# etapa1_anger_X.net
KiCad netlist of a schematic drawn in Altium Designer
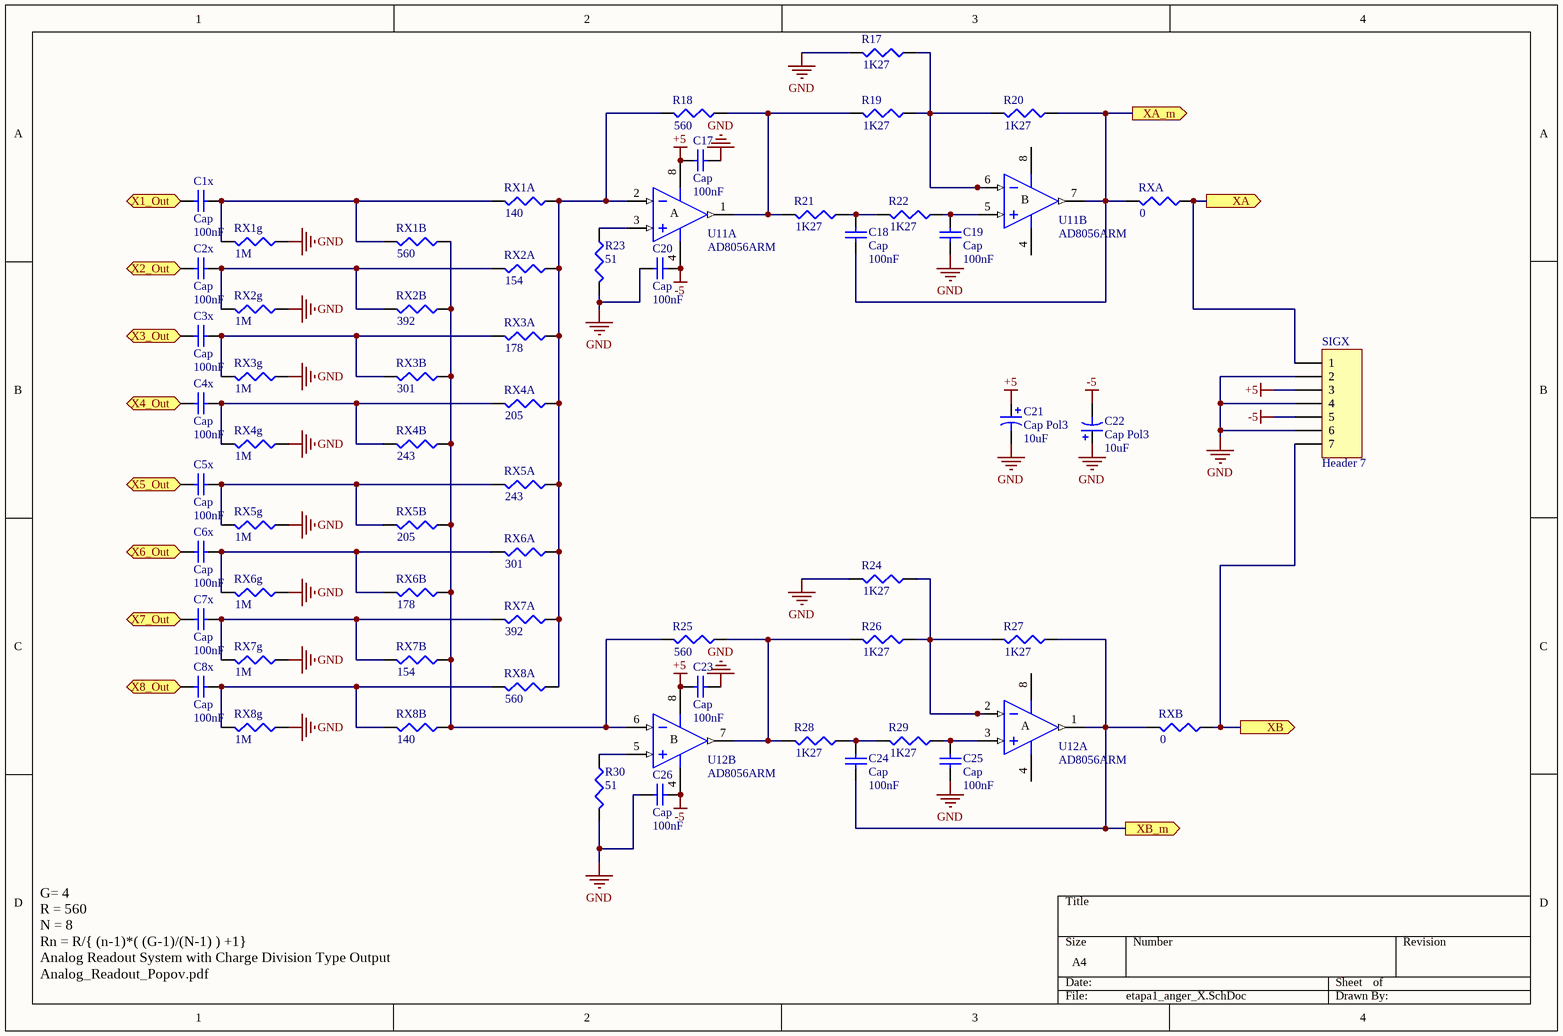
[diagram p0: etapa1_anger_X.SchDoc]

(export (version "E")
  (design (tool "Eeschema 10.0.6"))
  (components
    (comp (ref "C1x")
      (value "Cap")
      (footprint "1608[0603]")
      (description "Capacitor")
      (fields (field (name "ALTIUM_VALUE") "100nF") (field (name "PUBLISHER") "Altium Limited"))
      (libsource (lib "Miscellaneous Devices") (part "Cap"))
    )
    (comp (ref "C2x")
      (value "Cap")
      (footprint "1608[0603]")
      (description "Capacitor")
      (fields (field (name "ALTIUM_VALUE") "100nF") (field (name "PUBLISHER") "Altium Limited"))
      (libsource (lib "Miscellaneous Devices") (part "Cap"))
    )
    (comp (ref "C3x")
      (value "Cap")
      (footprint "1608[0603]")
      (description "Capacitor")
      (fields (field (name "ALTIUM_VALUE") "100nF") (field (name "PUBLISHER") "Altium Limited"))
      (libsource (lib "Miscellaneous Devices") (part "Cap"))
    )
    (comp (ref "C4x")
      (value "Cap")
      (footprint "1608[0603]")
      (description "Capacitor")
      (fields (field (name "ALTIUM_VALUE") "100nF") (field (name "PUBLISHER") "Altium Limited"))
      (libsource (lib "Miscellaneous Devices") (part "Cap"))
    )
    (comp (ref "C5x")
      (value "Cap")
      (footprint "1608[0603]")
      (description "Capacitor")
      (fields (field (name "ALTIUM_VALUE") "100nF") (field (name "PUBLISHER") "Altium Limited"))
      (libsource (lib "Miscellaneous Devices") (part "Cap"))
    )
    (comp (ref "C6x")
      (value "Cap")
      (footprint "1608[0603]")
      (description "Capacitor")
      (fields (field (name "ALTIUM_VALUE") "100nF") (field (name "PUBLISHER") "Altium Limited"))
      (libsource (lib "Miscellaneous Devices") (part "Cap"))
    )
    (comp (ref "C7x")
      (value "Cap")
      (footprint "1608[0603]")
      (description "Capacitor")
      (fields (field (name "ALTIUM_VALUE") "100nF") (field (name "PUBLISHER") "Altium Limited"))
      (libsource (lib "Miscellaneous Devices") (part "Cap"))
    )
    (comp (ref "C8x")
      (value "Cap")
      (footprint "1608[0603]")
      (description "Capacitor")
      (fields (field (name "ALTIUM_VALUE") "100nF") (field (name "PUBLISHER") "Altium Limited"))
      (libsource (lib "Miscellaneous Devices") (part "Cap"))
    )
    (comp (ref "C17")
      (value "Cap")
      (footprint "1608[0603]")
      (description "Capacitor")
      (fields (field (name "ALTIUM_VALUE") "100nF") (field (name "PUBLISHER") "Altium Limited"))
      (libsource (lib "Miscellaneous Devices") (part "Cap"))
    )
    (comp (ref "C18")
      (value "Cap")
      (footprint "1608[0603]")
      (description "Capacitor")
      (fields (field (name "ALTIUM_VALUE") "100nF") (field (name "PUBLISHER") "Altium Limited"))
      (libsource (lib "Miscellaneous Devices") (part "Cap"))
    )
    (comp (ref "C19")
      (value "Cap")
      (footprint "1608[0603]")
      (description "Capacitor")
      (fields (field (name "ALTIUM_VALUE") "100nF") (field (name "PUBLISHER") "Altium Limited"))
      (libsource (lib "Miscellaneous Devices") (part "Cap"))
    )
    (comp (ref "C20")
      (value "Cap")
      (footprint "1608[0603]")
      (description "Capacitor")
      (fields (field (name "ALTIUM_VALUE") "100nF") (field (name "PUBLISHER") "Altium Limited"))
      (libsource (lib "Miscellaneous Devices") (part "Cap"))
    )
    (comp (ref "C21")
      (value "Cap Pol3")
      (footprint "C0805")
      (description "Polarized Capacitor (Surface Mount)")
      (fields (field (name "ALTIUM_VALUE") "10uF") (field (name "PUBLISHER") "Altium Limited"))
      (libsource (lib "Miscellaneous Devices") (part "Cap Pol3"))
    )
    (comp (ref "C22")
      (value "Cap Pol3")
      (footprint "C0805")
      (description "Polarized Capacitor (Surface Mount)")
      (fields (field (name "ALTIUM_VALUE") "10uF") (field (name "PUBLISHER") "Altium Limited"))
      (libsource (lib "Miscellaneous Devices") (part "Cap Pol3"))
    )
    (comp (ref "C23")
      (value "Cap")
      (footprint "1608[0603]")
      (description "Capacitor")
      (fields (field (name "ALTIUM_VALUE") "100nF") (field (name "PUBLISHER") "Altium Limited"))
      (libsource (lib "Miscellaneous Devices") (part "Cap"))
    )
    (comp (ref "C24")
      (value "Cap")
      (footprint "1608[0603]")
      (description "Capacitor")
      (fields (field (name "ALTIUM_VALUE") "100nF") (field (name "PUBLISHER") "Altium Limited"))
      (libsource (lib "Miscellaneous Devices") (part "Cap"))
    )
    (comp (ref "C25")
      (value "Cap")
      (footprint "1608[0603]")
      (description "Capacitor")
      (fields (field (name "ALTIUM_VALUE") "100nF") (field (name "PUBLISHER") "Altium Limited"))
      (libsource (lib "Miscellaneous Devices") (part "Cap"))
    )
    (comp (ref "C26")
      (value "Cap")
      (footprint "1608[0603]")
      (description "Capacitor")
      (fields (field (name "ALTIUM_VALUE") "100nF") (field (name "PUBLISHER") "Altium Limited"))
      (libsource (lib "Miscellaneous Devices") (part "Cap"))
    )
    (comp (ref "R17")
      (value "1K27")
      (footprint "1608[0603]")
      (description "Resistor")
      (fields (field (name "Comment") "Res3") (field (name "PUBLISHER") "Altium Limited"))
      (libsource (lib "Miscellaneous Devices") (part "Res3"))
    )
    (comp (ref "R18")
      (value "560")
      (footprint "0402")
      (description "Resistor")
      (fields (field (name "Comment") "Res3") (field (name "PUBLISHER") "Altium Limited"))
      (libsource (lib "Miscellaneous Devices") (part "Res3"))
    )
    (comp (ref "R19")
      (value "1K27")
      (footprint "0402")
      (description "Resistor")
      (fields (field (name "Comment") "Res3") (field (name "PUBLISHER") "Altium Limited"))
      (libsource (lib "Miscellaneous Devices") (part "Res3"))
    )
    (comp (ref "R20")
      (value "1K27")
      (footprint "0402")
      (description "Resistor")
      (fields (field (name "Comment") "Res3") (field (name "PUBLISHER") "Altium Limited"))
      (libsource (lib "Miscellaneous Devices") (part "Res3"))
    )
    (comp (ref "R21")
      (value "1K27")
      (footprint "0402")
      (description "Resistor")
      (fields (field (name "Comment") "Res3") (field (name "PUBLISHER") "Altium Limited"))
      (libsource (lib "Miscellaneous Devices") (part "Res3"))
    )
    (comp (ref "R22")
      (value "1K27")
      (footprint "0402")
      (description "Resistor")
      (fields (field (name "Comment") "Res3") (field (name "PUBLISHER") "Altium Limited"))
      (libsource (lib "Miscellaneous Devices") (part "Res3"))
    )
    (comp (ref "R23")
      (value "51")
      (footprint "0402")
      (description "Resistor")
      (fields (field (name "Comment") "Res3") (field (name "PUBLISHER") "Altium Limited"))
      (libsource (lib "Miscellaneous Devices") (part "Res3"))
    )
    (comp (ref "R24")
      (value "1K27")
      (footprint "1608[0603]")
      (description "Resistor")
      (fields (field (name "Comment") "Res3") (field (name "PUBLISHER") "Altium Limited"))
      (libsource (lib "Miscellaneous Devices") (part "Res3"))
    )
    (comp (ref "R25")
      (value "560")
      (footprint "0402")
      (description "Resistor")
      (fields (field (name "Comment") "Res3") (field (name "PUBLISHER") "Altium Limited"))
      (libsource (lib "Miscellaneous Devices") (part "Res3"))
    )
    (comp (ref "R26")
      (value "1K27")
      (footprint "0402")
      (description "Resistor")
      (fields (field (name "Comment") "Res3") (field (name "PUBLISHER") "Altium Limited"))
      (libsource (lib "Miscellaneous Devices") (part "Res3"))
    )
    (comp (ref "R27")
      (value "1K27")
      (footprint "0402")
      (description "Resistor")
      (fields (field (name "Comment") "Res3") (field (name "PUBLISHER") "Altium Limited"))
      (libsource (lib "Miscellaneous Devices") (part "Res3"))
    )
    (comp (ref "R28")
      (value "1K27")
      (footprint "0402")
      (description "Resistor")
      (fields (field (name "Comment") "Res3") (field (name "PUBLISHER") "Altium Limited"))
      (libsource (lib "Miscellaneous Devices") (part "Res3"))
    )
    (comp (ref "R29")
      (value "1K27")
      (footprint "0402")
      (description "Resistor")
      (fields (field (name "Comment") "Res3") (field (name "PUBLISHER") "Altium Limited"))
      (libsource (lib "Miscellaneous Devices") (part "Res3"))
    )
    (comp (ref "R30")
      (value "51")
      (footprint "0402")
      (description "Resistor")
      (fields (field (name "Comment") "Res3") (field (name "PUBLISHER") "Altium Limited"))
      (libsource (lib "Miscellaneous Devices") (part "Res3"))
    )
    (comp (ref "RX1A")
      (value "140")
      (footprint "0402")
      (description "Resistor")
      (fields (field (name "Comment") "Res3") (field (name "PUBLISHER") "Altium Limited"))
      (libsource (lib "Miscellaneous Devices") (part "Res3"))
    )
    (comp (ref "RX1B")
      (value "560")
      (footprint "0402")
      (description "Resistor")
      (fields (field (name "Comment") "Res3") (field (name "PUBLISHER") "Altium Limited"))
      (libsource (lib "Miscellaneous Devices") (part "Res3"))
    )
    (comp (ref "RX1g")
      (value "1M")
      (footprint "J1-0603")
      (description "Resistor")
      (fields (field (name "Comment") "Res3") (field (name "PUBLISHER") "Altium Limited"))
      (libsource (lib "Miscellaneous Devices") (part "Res3"))
    )
    (comp (ref "RX2A")
      (value "154")
      (footprint "0402")
      (description "Resistor")
      (fields (field (name "Comment") "Res3") (field (name "PUBLISHER") "Altium Limited"))
      (libsource (lib "Miscellaneous Devices") (part "Res3"))
    )
    (comp (ref "RX2B")
      (value "392")
      (footprint "0402")
      (description "Resistor")
      (fields (field (name "Comment") "Res3") (field (name "PUBLISHER") "Altium Limited"))
      (libsource (lib "Miscellaneous Devices") (part "Res3"))
    )
    (comp (ref "RX2g")
      (value "1M")
      (footprint "J1-0603")
      (description "Resistor")
      (fields (field (name "Comment") "Res3") (field (name "PUBLISHER") "Altium Limited"))
      (libsource (lib "Miscellaneous Devices") (part "Res3"))
    )
    (comp (ref "RX3A")
      (value "178")
      (footprint "0402")
      (description "Resistor")
      (fields (field (name "Comment") "Res3") (field (name "PUBLISHER") "Altium Limited"))
      (libsource (lib "Miscellaneous Devices") (part "Res3"))
    )
    (comp (ref "RX3B")
      (value "301")
      (footprint "0402")
      (description "Resistor")
      (fields (field (name "Comment") "Res3") (field (name "PUBLISHER") "Altium Limited"))
      (libsource (lib "Miscellaneous Devices") (part "Res3"))
    )
    (comp (ref "RX3g")
      (value "1M")
      (footprint "J1-0603")
      (description "Resistor")
      (fields (field (name "Comment") "Res3") (field (name "PUBLISHER") "Altium Limited"))
      (libsource (lib "Miscellaneous Devices") (part "Res3"))
    )
    (comp (ref "RX4A")
      (value "205")
      (footprint "0402")
      (description "Resistor")
      (fields (field (name "Comment") "Res3") (field (name "PUBLISHER") "Altium Limited"))
      (libsource (lib "Miscellaneous Devices") (part "Res3"))
    )
    (comp (ref "RX4B")
      (value "243")
      (footprint "0402")
      (description "Resistor")
      (fields (field (name "Comment") "Res3") (field (name "PUBLISHER") "Altium Limited"))
      (libsource (lib "Miscellaneous Devices") (part "Res3"))
    )
    (comp (ref "RX4g")
      (value "1M")
      (footprint "J1-0603")
      (description "Resistor")
      (fields (field (name "Comment") "Res3") (field (name "PUBLISHER") "Altium Limited"))
      (libsource (lib "Miscellaneous Devices") (part "Res3"))
    )
    (comp (ref "RX5A")
      (value "243")
      (footprint "0402")
      (description "Resistor")
      (fields (field (name "Comment") "Res3") (field (name "PUBLISHER") "Altium Limited"))
      (libsource (lib "Miscellaneous Devices") (part "Res3"))
    )
    (comp (ref "RX5B")
      (value "205")
      (footprint "0402")
      (description "Resistor")
      (fields (field (name "Comment") "Res3") (field (name "PUBLISHER") "Altium Limited"))
      (libsource (lib "Miscellaneous Devices") (part "Res3"))
    )
    (comp (ref "RX5g")
      (value "1M")
      (footprint "J1-0603")
      (description "Resistor")
      (fields (field (name "Comment") "Res3") (field (name "PUBLISHER") "Altium Limited"))
      (libsource (lib "Miscellaneous Devices") (part "Res3"))
    )
    (comp (ref "RX6A")
      (value "301")
      (footprint "0402")
      (description "Resistor")
      (fields (field (name "Comment") "Res3") (field (name "PUBLISHER") "Altium Limited"))
      (libsource (lib "Miscellaneous Devices") (part "Res3"))
    )
    (comp (ref "RX6B")
      (value "178")
      (footprint "0402")
      (description "Resistor")
      (fields (field (name "Comment") "Res3") (field (name "PUBLISHER") "Altium Limited"))
      (libsource (lib "Miscellaneous Devices") (part "Res3"))
    )
    (comp (ref "RX6g")
      (value "1M")
      (footprint "J1-0603")
      (description "Resistor")
      (fields (field (name "Comment") "Res3") (field (name "PUBLISHER") "Altium Limited"))
      (libsource (lib "Miscellaneous Devices") (part "Res3"))
    )
    (comp (ref "RX7A")
      (value "392")
      (footprint "0402")
      (description "Resistor")
      (fields (field (name "Comment") "Res3") (field (name "PUBLISHER") "Altium Limited"))
      (libsource (lib "Miscellaneous Devices") (part "Res3"))
    )
    (comp (ref "RX7B")
      (value "154")
      (footprint "0402")
      (description "Resistor")
      (fields (field (name "Comment") "Res3") (field (name "PUBLISHER") "Altium Limited"))
      (libsource (lib "Miscellaneous Devices") (part "Res3"))
    )
    (comp (ref "RX7g")
      (value "1M")
      (footprint "J1-0603")
      (description "Resistor")
      (fields (field (name "Comment") "Res3") (field (name "PUBLISHER") "Altium Limited"))
      (libsource (lib "Miscellaneous Devices") (part "Res3"))
    )
    (comp (ref "RX8A")
      (value "560")
      (footprint "0402")
      (description "Resistor")
      (fields (field (name "Comment") "Res3") (field (name "PUBLISHER") "Altium Limited"))
      (libsource (lib "Miscellaneous Devices") (part "Res3"))
    )
    (comp (ref "RX8B")
      (value "140")
      (footprint "0402")
      (description "Resistor")
      (fields (field (name "Comment") "Res3") (field (name "PUBLISHER") "Altium Limited"))
      (libsource (lib "Miscellaneous Devices") (part "Res3"))
    )
    (comp (ref "RX8g")
      (value "1M")
      (footprint "J1-0603")
      (description "Resistor")
      (fields (field (name "Comment") "Res3") (field (name "PUBLISHER") "Altium Limited"))
      (libsource (lib "Miscellaneous Devices") (part "Res3"))
    )
    (comp (ref "RXA")
      (value "0")
      (footprint "0402")
      (description "Resistor")
      (fields (field (name "Comment") "Res3") (field (name "PUBLISHER") "Altium Limited"))
      (libsource (lib "Miscellaneous Devices") (part "Res3"))
    )
    (comp (ref "RXB")
      (value "0")
      (footprint "0402")
      (description "Resistor")
      (fields (field (name "Comment") "Res3") (field (name "PUBLISHER") "Altium Limited"))
      (libsource (lib "Miscellaneous Devices") (part "Res3"))
    )
    (comp (ref "SIGX")
      (value "Header 7")
      (footprint "HDR1X7")
      (description "Header, 7-Pin")
      (fields (field (name "PUBLISHER") "Altium Limited"))
      (libsource (lib "Miscellaneous Connectors") (part "Header 7"))
    )
    (comp (ref "U11")
      (value "AD8056ARM")
      (footprint "RM-8")
      (description "Low Cost, 300MHz Voltage Feedback Amplifier")
      (fields (field (name "PUBLISHER") "Altium Limited"))
      (libsource (lib "AD Operational Amplifier") (part "AD8056ARM"))
    )
    (comp (ref "U12")
      (value "AD8056ARM")
      (footprint "RM-8")
      (description "Low Cost, 300MHz Voltage Feedback Amplifier")
      (fields (field (name "PUBLISHER") "Altium Limited"))
      (libsource (lib "AD Operational Amplifier") (part "AD8056ARM"))
    )
  )
  (nets
    (net (code "1") (name "+5") (class "Default")
      (node (ref "C17") (pin "1") (pinfunction "1_1") (pintype "passive"))
      (node (ref "C21") (pin "1") (pinfunction "1_1") (pintype "passive"))
      (node (ref "C23") (pin "1") (pinfunction "1_1") (pintype "passive"))
      (node (ref "SIGX") (pin "3") (pinfunction "3_3") (pintype "passive"))
      (node (ref "U11") (pin "8") (pinfunction "V+_8") (pintype "power_in"))
      (node (ref "U12") (pin "8") (pinfunction "V+_8") (pintype "power_in"))
    )
    (net (code "2") (name "-5") (class "Default")
      (node (ref "C20") (pin "2") (pinfunction "2_2") (pintype "passive"))
      (node (ref "C22") (pin "2") (pinfunction "2_2") (pintype "passive"))
      (node (ref "C26") (pin "2") (pinfunction "2_2") (pintype "passive"))
      (node (ref "SIGX") (pin "5") (pinfunction "5_5") (pintype "passive"))
      (node (ref "U11") (pin "4") (pinfunction "V-_4") (pintype "power_in"))
      (node (ref "U12") (pin "4") (pinfunction "V-_4") (pintype "power_in"))
    )
    (net (code "3") (name "/X1_Out") (class "Default")
      (node (ref "C1x") (pin "1") (pinfunction "1_1") (pintype "passive"))
    )
    (net (code "4") (name "/X2_Out") (class "Default")
      (node (ref "C2x") (pin "1") (pinfunction "1_1") (pintype "passive"))
    )
    (net (code "5") (name "/X3_Out") (class "Default")
      (node (ref "C3x") (pin "1") (pinfunction "1_1") (pintype "passive"))
    )
    (net (code "6") (name "/X4_Out") (class "Default")
      (node (ref "C4x") (pin "1") (pinfunction "1_1") (pintype "passive"))
    )
    (net (code "7") (name "/X5_Out") (class "Default")
      (node (ref "C5x") (pin "1") (pinfunction "1_1") (pintype "passive"))
    )
    (net (code "8") (name "/X6_Out") (class "Default")
      (node (ref "C6x") (pin "1") (pinfunction "1_1") (pintype "passive"))
    )
    (net (code "9") (name "/X7_Out") (class "Default")
      (node (ref "C7x") (pin "1") (pinfunction "1_1") (pintype "passive"))
    )
    (net (code "10") (name "/X8_Out") (class "Default")
      (node (ref "C8x") (pin "1") (pinfunction "1_1") (pintype "passive"))
    )
    (net (code "11") (name "/XA") (class "Default")
      (node (ref "RXA") (pin "1") (pinfunction "1_1") (pintype "passive"))
      (node (ref "SIGX") (pin "1") (pinfunction "1_1") (pintype "passive"))
    )
    (net (code "12") (name "/XA_m") (class "Default")
      (node (ref "C18") (pin "2") (pinfunction "2_2") (pintype "passive"))
      (node (ref "R20") (pin "1") (pinfunction "1_1") (pintype "passive"))
      (node (ref "RXA") (pin "2") (pinfunction "2_2") (pintype "passive"))
      (node (ref "U11") (pin "7") (pinfunction "OUT_7") (pintype "output"))
    )
    (net (code "13") (name "/XB") (class "Default")
      (node (ref "RXB") (pin "1") (pinfunction "1_1") (pintype "passive"))
      (node (ref "SIGX") (pin "7") (pinfunction "7_7") (pintype "passive"))
    )
    (net (code "14") (name "/XB_m") (class "Default")
      (node (ref "C24") (pin "2") (pinfunction "2_2") (pintype "passive"))
      (node (ref "R27") (pin "1") (pinfunction "1_1") (pintype "passive"))
      (node (ref "RXB") (pin "2") (pinfunction "2_2") (pintype "passive"))
      (node (ref "U12") (pin "1") (pinfunction "OUT_1") (pintype "output"))
    )
    (net (code "15") (name "GND") (class "Default")
      (node (ref "C17") (pin "2") (pinfunction "2_2") (pintype "passive"))
      (node (ref "C19") (pin "2") (pinfunction "2_2") (pintype "passive"))
      (node (ref "C20") (pin "1") (pinfunction "1_1") (pintype "passive"))
      (node (ref "C21") (pin "2") (pinfunction "2_2") (pintype "passive"))
      (node (ref "C22") (pin "1") (pinfunction "1_1") (pintype "passive"))
      (node (ref "C23") (pin "2") (pinfunction "2_2") (pintype "passive"))
      (node (ref "C25") (pin "2") (pinfunction "2_2") (pintype "passive"))
      (node (ref "C26") (pin "1") (pinfunction "1_1") (pintype "passive"))
      (node (ref "R17") (pin "2") (pinfunction "2_2") (pintype "passive"))
      (node (ref "R23") (pin "2") (pinfunction "2_2") (pintype "passive"))
      (node (ref "R24") (pin "2") (pinfunction "2_2") (pintype "passive"))
      (node (ref "R30") (pin "2") (pinfunction "2_2") (pintype "passive"))
      (node (ref "RX1g") (pin "1") (pinfunction "1_1") (pintype "passive"))
      (node (ref "RX2g") (pin "1") (pinfunction "1_1") (pintype "passive"))
      (node (ref "RX3g") (pin "1") (pinfunction "1_1") (pintype "passive"))
      (node (ref "RX4g") (pin "1") (pinfunction "1_1") (pintype "passive"))
      (node (ref "RX5g") (pin "1") (pinfunction "1_1") (pintype "passive"))
      (node (ref "RX6g") (pin "1") (pinfunction "1_1") (pintype "passive"))
      (node (ref "RX7g") (pin "1") (pinfunction "1_1") (pintype "passive"))
      (node (ref "RX8g") (pin "1") (pinfunction "1_1") (pintype "passive"))
      (node (ref "SIGX") (pin "2") (pinfunction "2_2") (pintype "passive"))
      (node (ref "SIGX") (pin "4") (pinfunction "4_4") (pintype "passive"))
      (node (ref "SIGX") (pin "6") (pinfunction "6_6") (pintype "passive"))
    )
    (net (code "16") (name "Net-(C1x-Pad2)") (class "Default")
      (node (ref "C1x") (pin "2") (pinfunction "2_2") (pintype "passive"))
      (node (ref "RX1A") (pin "2") (pinfunction "2_2") (pintype "passive"))
      (node (ref "RX1B") (pin "2") (pinfunction "2_2") (pintype "passive"))
      (node (ref "RX1g") (pin "2") (pinfunction "2_2") (pintype "passive"))
    )
    (net (code "17") (name "Net-(C2x-Pad2)") (class "Default")
      (node (ref "C2x") (pin "2") (pinfunction "2_2") (pintype "passive"))
      (node (ref "RX2A") (pin "2") (pinfunction "2_2") (pintype "passive"))
      (node (ref "RX2B") (pin "2") (pinfunction "2_2") (pintype "passive"))
      (node (ref "RX2g") (pin "2") (pinfunction "2_2") (pintype "passive"))
    )
    (net (code "18") (name "Net-(C3x-Pad2)") (class "Default")
      (node (ref "C3x") (pin "2") (pinfunction "2_2") (pintype "passive"))
      (node (ref "RX3A") (pin "2") (pinfunction "2_2") (pintype "passive"))
      (node (ref "RX3B") (pin "2") (pinfunction "2_2") (pintype "passive"))
      (node (ref "RX3g") (pin "2") (pinfunction "2_2") (pintype "passive"))
    )
    (net (code "19") (name "Net-(C4x-Pad2)") (class "Default")
      (node (ref "C4x") (pin "2") (pinfunction "2_2") (pintype "passive"))
      (node (ref "RX4A") (pin "2") (pinfunction "2_2") (pintype "passive"))
      (node (ref "RX4B") (pin "2") (pinfunction "2_2") (pintype "passive"))
      (node (ref "RX4g") (pin "2") (pinfunction "2_2") (pintype "passive"))
    )
    (net (code "20") (name "Net-(C5x-Pad2)") (class "Default")
      (node (ref "C5x") (pin "2") (pinfunction "2_2") (pintype "passive"))
      (node (ref "RX5A") (pin "2") (pinfunction "2_2") (pintype "passive"))
      (node (ref "RX5B") (pin "2") (pinfunction "2_2") (pintype "passive"))
      (node (ref "RX5g") (pin "2") (pinfunction "2_2") (pintype "passive"))
    )
    (net (code "21") (name "Net-(C6x-Pad2)") (class "Default")
      (node (ref "C6x") (pin "2") (pinfunction "2_2") (pintype "passive"))
      (node (ref "RX6A") (pin "2") (pinfunction "2_2") (pintype "passive"))
      (node (ref "RX6B") (pin "2") (pinfunction "2_2") (pintype "passive"))
      (node (ref "RX6g") (pin "2") (pinfunction "2_2") (pintype "passive"))
    )
    (net (code "22") (name "Net-(C7x-Pad2)") (class "Default")
      (node (ref "C7x") (pin "2") (pinfunction "2_2") (pintype "passive"))
      (node (ref "RX7A") (pin "2") (pinfunction "2_2") (pintype "passive"))
      (node (ref "RX7B") (pin "2") (pinfunction "2_2") (pintype "passive"))
      (node (ref "RX7g") (pin "2") (pinfunction "2_2") (pintype "passive"))
    )
    (net (code "23") (name "Net-(C8x-Pad2)") (class "Default")
      (node (ref "C8x") (pin "2") (pinfunction "2_2") (pintype "passive"))
      (node (ref "RX8A") (pin "2") (pinfunction "2_2") (pintype "passive"))
      (node (ref "RX8B") (pin "2") (pinfunction "2_2") (pintype "passive"))
      (node (ref "RX8g") (pin "2") (pinfunction "2_2") (pintype "passive"))
    )
    (net (code "24") (name "Net-(C18-Pad1)") (class "Default")
      (node (ref "C18") (pin "1") (pinfunction "1_1") (pintype "passive"))
      (node (ref "R21") (pin "1") (pinfunction "1_1") (pintype "passive"))
      (node (ref "R22") (pin "2") (pinfunction "2_2") (pintype "passive"))
    )
    (net (code "25") (name "Net-(C24-Pad1)") (class "Default")
      (node (ref "C24") (pin "1") (pinfunction "1_1") (pintype "passive"))
      (node (ref "R28") (pin "1") (pinfunction "1_1") (pintype "passive"))
      (node (ref "R29") (pin "2") (pinfunction "2_2") (pintype "passive"))
    )
    (net (code "26") (name "Net-(U11A-IN+)") (class "Default")
      (node (ref "R23") (pin "1") (pinfunction "1_1") (pintype "passive"))
      (node (ref "U11") (pin "3") (pinfunction "IN+_3") (pintype "input"))
    )
    (net (code "27") (name "Net-(U11A-IN-)") (class "Default")
      (node (ref "R18") (pin "2") (pinfunction "2_2") (pintype "passive"))
      (node (ref "RX1A") (pin "1") (pinfunction "1_1") (pintype "passive"))
      (node (ref "RX2A") (pin "1") (pinfunction "1_1") (pintype "passive"))
      (node (ref "RX3A") (pin "1") (pinfunction "1_1") (pintype "passive"))
      (node (ref "RX4A") (pin "1") (pinfunction "1_1") (pintype "passive"))
      (node (ref "RX5A") (pin "1") (pinfunction "1_1") (pintype "passive"))
      (node (ref "RX6A") (pin "1") (pinfunction "1_1") (pintype "passive"))
      (node (ref "RX7A") (pin "1") (pinfunction "1_1") (pintype "passive"))
      (node (ref "RX8A") (pin "1") (pinfunction "1_1") (pintype "passive"))
      (node (ref "U11") (pin "2") (pinfunction "IN-_2") (pintype "input"))
    )
    (net (code "28") (name "Net-(U11A-OUT)") (class "Default")
      (node (ref "R18") (pin "1") (pinfunction "1_1") (pintype "passive"))
      (node (ref "R19") (pin "2") (pinfunction "2_2") (pintype "passive"))
      (node (ref "R21") (pin "2") (pinfunction "2_2") (pintype "passive"))
      (node (ref "U11") (pin "1") (pinfunction "OUT_1") (pintype "output"))
    )
    (net (code "29") (name "Net-(U11B-IN+)") (class "Default")
      (node (ref "C19") (pin "1") (pinfunction "1_1") (pintype "passive"))
      (node (ref "R22") (pin "1") (pinfunction "1_1") (pintype "passive"))
      (node (ref "U11") (pin "5") (pinfunction "IN+_5") (pintype "input"))
    )
    (net (code "30") (name "Net-(U11B-IN-)") (class "Default")
      (node (ref "R17") (pin "1") (pinfunction "1_1") (pintype "passive"))
      (node (ref "R19") (pin "1") (pinfunction "1_1") (pintype "passive"))
      (node (ref "R20") (pin "2") (pinfunction "2_2") (pintype "passive"))
      (node (ref "U11") (pin "6") (pinfunction "IN-_6") (pintype "input"))
    )
    (net (code "31") (name "Net-(U12A-IN+)") (class "Default")
      (node (ref "C25") (pin "1") (pinfunction "1_1") (pintype "passive"))
      (node (ref "R29") (pin "1") (pinfunction "1_1") (pintype "passive"))
      (node (ref "U12") (pin "3") (pinfunction "IN+_3") (pintype "input"))
    )
    (net (code "32") (name "Net-(U12A-IN-)") (class "Default")
      (node (ref "R24") (pin "1") (pinfunction "1_1") (pintype "passive"))
      (node (ref "R26") (pin "1") (pinfunction "1_1") (pintype "passive"))
      (node (ref "R27") (pin "2") (pinfunction "2_2") (pintype "passive"))
      (node (ref "U12") (pin "2") (pinfunction "IN-_2") (pintype "input"))
    )
    (net (code "33") (name "Net-(U12B-IN+)") (class "Default")
      (node (ref "R30") (pin "1") (pinfunction "1_1") (pintype "passive"))
      (node (ref "U12") (pin "5") (pinfunction "IN+_5") (pintype "input"))
    )
    (net (code "34") (name "Net-(U12B-IN-)") (class "Default")
      (node (ref "R25") (pin "2") (pinfunction "2_2") (pintype "passive"))
      (node (ref "RX1B") (pin "1") (pinfunction "1_1") (pintype "passive"))
      (node (ref "RX2B") (pin "1") (pinfunction "1_1") (pintype "passive"))
      (node (ref "RX3B") (pin "1") (pinfunction "1_1") (pintype "passive"))
      (node (ref "RX4B") (pin "1") (pinfunction "1_1") (pintype "passive"))
      (node (ref "RX5B") (pin "1") (pinfunction "1_1") (pintype "passive"))
      (node (ref "RX6B") (pin "1") (pinfunction "1_1") (pintype "passive"))
      (node (ref "RX7B") (pin "1") (pinfunction "1_1") (pintype "passive"))
      (node (ref "RX8B") (pin "1") (pinfunction "1_1") (pintype "passive"))
      (node (ref "U12") (pin "6") (pinfunction "IN-_6") (pintype "input"))
    )
    (net (code "35") (name "Net-(U12B-OUT)") (class "Default")
      (node (ref "R25") (pin "1") (pinfunction "1_1") (pintype "passive"))
      (node (ref "R26") (pin "2") (pinfunction "2_2") (pintype "passive"))
      (node (ref "R28") (pin "2") (pinfunction "2_2") (pintype "passive"))
      (node (ref "U12") (pin "7") (pinfunction "OUT_7") (pintype "output"))
    )
    (net (code "36") (name "unconnected-(U11B-V+-Pad8)") (class "Default")
      (node (ref "U11") (pin "8") (pinfunction "V+_8") (pintype "power_in"))
    )
    (net (code "37") (name "unconnected-(U11B-V--Pad4)") (class "Default")
      (node (ref "U11") (pin "4") (pinfunction "V-_4") (pintype "power_in"))
    )
    (net (code "38") (name "unconnected-(U12A-V+-Pad8)") (class "Default")
      (node (ref "U12") (pin "8") (pinfunction "V+_8") (pintype "power_in"))
    )
    (net (code "39") (name "unconnected-(U12A-V--Pad4)") (class "Default")
      (node (ref "U12") (pin "4") (pinfunction "V-_4") (pintype "power_in"))
    )
  )
)
